# Connectors.net
KiCad netlist of a schematic drawn in Altium Designer
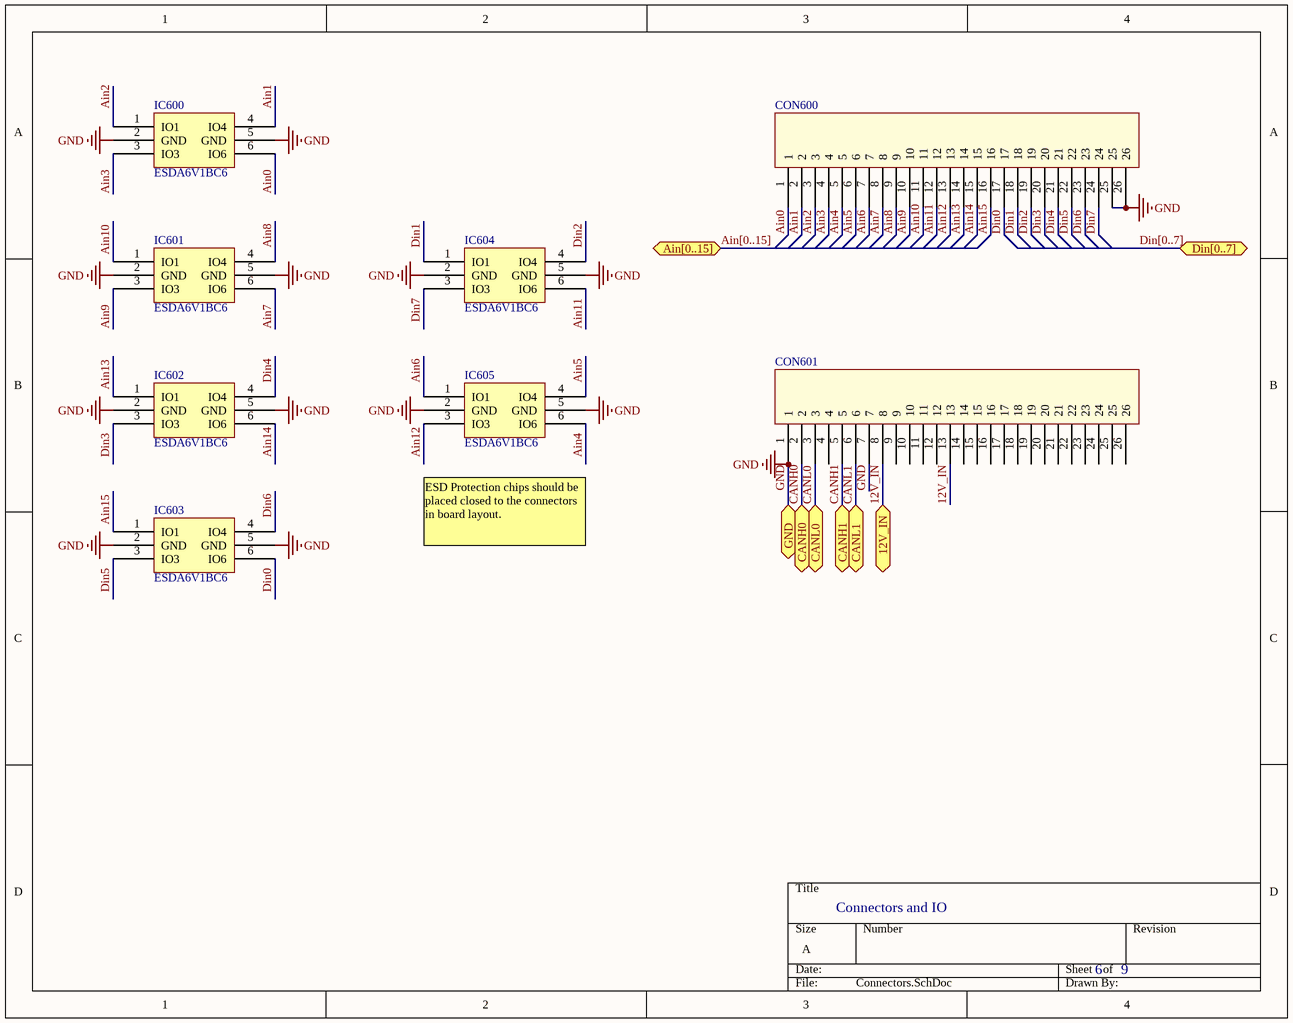
[diagram p0: Connectors.SchDoc]

(export (version "E")
  (design (tool "Eeschema 10.0.6"))
  (components
    (comp (ref "CON600")
      (value "26 Pin Conn")
      (footprint "AMP SuperSeal 1.0 26pin")
      (description "AMP SuperSeal 1.0 26 Pin")
      (libsource (lib "Components") (part "AMP_26Pin"))
    )
    (comp (ref "CON601")
      (value "26 Pin Conn")
      (footprint "AMP SuperSeal 1.0 26pin")
      (description "AMP SuperSeal 1.0 26 Pin")
      (libsource (lib "Components") (part "AMP_26Pin"))
    )
    (comp (ref "IC600")
      (value "ESDA6V1BC6")
      (footprint "SOT23-6L")
      (description "4 channel bi directional ESD protection")
      (libsource (lib "Components") (part "ESDA6V1BC6"))
    )
    (comp (ref "IC601")
      (value "ESDA6V1BC6")
      (footprint "SOT23-6L")
      (description "4 channel bi directional ESD protection")
      (libsource (lib "Components") (part "ESDA6V1BC6"))
    )
    (comp (ref "IC602")
      (value "ESDA6V1BC6")
      (footprint "SOT23-6L")
      (description "4 channel bi directional ESD protection")
      (libsource (lib "Components") (part "ESDA6V1BC6"))
    )
    (comp (ref "IC603")
      (value "ESDA6V1BC6")
      (footprint "SOT23-6L")
      (description "4 channel bi directional ESD protection")
      (libsource (lib "Components") (part "ESDA6V1BC6"))
    )
    (comp (ref "IC604")
      (value "ESDA6V1BC6")
      (footprint "SOT23-6L")
      (description "4 channel bi directional ESD protection")
      (libsource (lib "Components") (part "ESDA6V1BC6"))
    )
    (comp (ref "IC605")
      (value "ESDA6V1BC6")
      (footprint "SOT23-6L")
      (description "4 channel bi directional ESD protection")
      (libsource (lib "Components") (part "ESDA6V1BC6"))
    )
  )
  (nets
    (net (code "1") (name "/12V_IN") (class "Default")
      (node (ref "CON601") (pin "13") (pinfunction "13_13") (pintype "passive"))
      (node (ref "CON601") (pin "8") (pinfunction "8_8") (pintype "passive"))
    )
    (net (code "2") (name "/Ain0") (class "Default")
      (node (ref "CON600") (pin "1") (pinfunction "1_1") (pintype "passive"))
      (node (ref "IC600") (pin "6") (pinfunction "IO6_6") (pintype "passive"))
    )
    (net (code "3") (name "/Ain1") (class "Default")
      (node (ref "CON600") (pin "2") (pinfunction "2_2") (pintype "passive"))
      (node (ref "IC600") (pin "4") (pinfunction "IO4_4") (pintype "passive"))
    )
    (net (code "4") (name "/Ain2") (class "Default")
      (node (ref "CON600") (pin "3") (pinfunction "3_3") (pintype "passive"))
      (node (ref "IC600") (pin "1") (pinfunction "IO1_1") (pintype "passive"))
    )
    (net (code "5") (name "/Ain3") (class "Default")
      (node (ref "CON600") (pin "4") (pinfunction "4_4") (pintype "passive"))
      (node (ref "IC600") (pin "3") (pinfunction "IO3_3") (pintype "passive"))
    )
    (net (code "6") (name "/Ain4") (class "Default")
      (node (ref "CON600") (pin "5") (pinfunction "5_5") (pintype "passive"))
      (node (ref "IC605") (pin "6") (pinfunction "IO6_6") (pintype "passive"))
    )
    (net (code "7") (name "/Ain5") (class "Default")
      (node (ref "CON600") (pin "6") (pinfunction "6_6") (pintype "passive"))
      (node (ref "IC605") (pin "4") (pinfunction "IO4_4") (pintype "passive"))
    )
    (net (code "8") (name "/Ain6") (class "Default")
      (node (ref "CON600") (pin "7") (pinfunction "7_7") (pintype "passive"))
      (node (ref "IC605") (pin "1") (pinfunction "IO1_1") (pintype "passive"))
    )
    (net (code "9") (name "/Ain7") (class "Default")
      (node (ref "CON600") (pin "8") (pinfunction "8_8") (pintype "passive"))
      (node (ref "IC601") (pin "6") (pinfunction "IO6_6") (pintype "passive"))
    )
    (net (code "10") (name "/Ain8") (class "Default")
      (node (ref "CON600") (pin "9") (pinfunction "9_9") (pintype "passive"))
      (node (ref "IC601") (pin "4") (pinfunction "IO4_4") (pintype "passive"))
    )
    (net (code "11") (name "/Ain9") (class "Default")
      (node (ref "CON600") (pin "10") (pinfunction "10_10") (pintype "passive"))
      (node (ref "IC601") (pin "3") (pinfunction "IO3_3") (pintype "passive"))
    )
    (net (code "12") (name "/Ain10") (class "Default")
      (node (ref "CON600") (pin "11") (pinfunction "11_11") (pintype "passive"))
      (node (ref "IC601") (pin "1") (pinfunction "IO1_1") (pintype "passive"))
    )
    (net (code "13") (name "/Ain11") (class "Default")
      (node (ref "CON600") (pin "12") (pinfunction "12_12") (pintype "passive"))
      (node (ref "IC604") (pin "6") (pinfunction "IO6_6") (pintype "passive"))
    )
    (net (code "14") (name "/Ain12") (class "Default")
      (node (ref "CON600") (pin "13") (pinfunction "13_13") (pintype "passive"))
      (node (ref "IC605") (pin "3") (pinfunction "IO3_3") (pintype "passive"))
    )
    (net (code "15") (name "/Ain13") (class "Default")
      (node (ref "CON600") (pin "14") (pinfunction "14_14") (pintype "passive"))
      (node (ref "IC602") (pin "1") (pinfunction "IO1_1") (pintype "passive"))
    )
    (net (code "16") (name "/Ain14") (class "Default")
      (node (ref "CON600") (pin "15") (pinfunction "15_15") (pintype "passive"))
      (node (ref "IC602") (pin "6") (pinfunction "IO6_6") (pintype "passive"))
    )
    (net (code "17") (name "/Ain15") (class "Default")
      (node (ref "CON600") (pin "16") (pinfunction "16_16") (pintype "passive"))
      (node (ref "IC603") (pin "1") (pinfunction "IO1_1") (pintype "passive"))
    )
    (net (code "19") (name "/CANH0") (class "Default")
      (node (ref "CON601") (pin "2") (pinfunction "2_2") (pintype "passive"))
    )
    (net (code "20") (name "/CANH1") (class "Default")
      (node (ref "CON601") (pin "5") (pinfunction "5_5") (pintype "passive"))
    )
    (net (code "21") (name "/CANL0") (class "Default")
      (node (ref "CON601") (pin "3") (pinfunction "3_3") (pintype "passive"))
    )
    (net (code "22") (name "/CANL1") (class "Default")
      (node (ref "CON601") (pin "6") (pinfunction "6_6") (pintype "passive"))
    )
    (net (code "23") (name "/Din0") (class "Default")
      (node (ref "CON600") (pin "17") (pinfunction "17_17") (pintype "passive"))
      (node (ref "IC603") (pin "6") (pinfunction "IO6_6") (pintype "passive"))
    )
    (net (code "24") (name "/Din1") (class "Default")
      (node (ref "CON600") (pin "18") (pinfunction "18_18") (pintype "passive"))
      (node (ref "IC604") (pin "1") (pinfunction "IO1_1") (pintype "passive"))
    )
    (net (code "25") (name "/Din2") (class "Default")
      (node (ref "CON600") (pin "19") (pinfunction "19_19") (pintype "passive"))
      (node (ref "IC604") (pin "4") (pinfunction "IO4_4") (pintype "passive"))
    )
    (net (code "26") (name "/Din3") (class "Default")
      (node (ref "CON600") (pin "20") (pinfunction "20_20") (pintype "passive"))
      (node (ref "IC602") (pin "3") (pinfunction "IO3_3") (pintype "passive"))
    )
    (net (code "27") (name "/Din4") (class "Default")
      (node (ref "CON600") (pin "21") (pinfunction "21_21") (pintype "passive"))
      (node (ref "IC602") (pin "4") (pinfunction "IO4_4") (pintype "passive"))
    )
    (net (code "28") (name "/Din5") (class "Default")
      (node (ref "CON600") (pin "22") (pinfunction "22_22") (pintype "passive"))
      (node (ref "IC603") (pin "3") (pinfunction "IO3_3") (pintype "passive"))
    )
    (net (code "29") (name "/Din6") (class "Default")
      (node (ref "CON600") (pin "23") (pinfunction "23_23") (pintype "passive"))
      (node (ref "IC603") (pin "4") (pinfunction "IO4_4") (pintype "passive"))
    )
    (net (code "30") (name "/Din7") (class "Default")
      (node (ref "CON600") (pin "24") (pinfunction "24_24") (pintype "passive"))
      (node (ref "IC604") (pin "3") (pinfunction "IO3_3") (pintype "passive"))
    )
    (net (code "32") (name "GND") (class "Default")
      (node (ref "CON600") (pin "25") (pinfunction "25_25") (pintype "passive"))
      (node (ref "CON600") (pin "26") (pinfunction "26_26") (pintype "passive"))
      (node (ref "CON601") (pin "1") (pinfunction "1_1") (pintype "passive"))
      (node (ref "CON601") (pin "7") (pinfunction "7_7") (pintype "passive"))
      (node (ref "IC600") (pin "2") (pinfunction "GND_2") (pintype "passive"))
      (node (ref "IC600") (pin "5") (pinfunction "GND_5") (pintype "passive"))
      (node (ref "IC601") (pin "2") (pinfunction "GND_2") (pintype "passive"))
      (node (ref "IC601") (pin "5") (pinfunction "GND_5") (pintype "passive"))
      (node (ref "IC602") (pin "2") (pinfunction "GND_2") (pintype "passive"))
      (node (ref "IC602") (pin "5") (pinfunction "GND_5") (pintype "passive"))
      (node (ref "IC603") (pin "2") (pinfunction "GND_2") (pintype "passive"))
      (node (ref "IC603") (pin "5") (pinfunction "GND_5") (pintype "passive"))
      (node (ref "IC604") (pin "2") (pinfunction "GND_2") (pintype "passive"))
      (node (ref "IC604") (pin "5") (pinfunction "GND_5") (pintype "passive"))
      (node (ref "IC605") (pin "2") (pinfunction "GND_2") (pintype "passive"))
      (node (ref "IC605") (pin "5") (pinfunction "GND_5") (pintype "passive"))
    )
    (net (code "33") (name "unconnected-(CON601-Pad4)") (class "Default")
      (node (ref "CON601") (pin "4") (pinfunction "4_4") (pintype "passive"))
    )
    (net (code "34") (name "unconnected-(CON601-Pad9)") (class "Default")
      (node (ref "CON601") (pin "9") (pinfunction "9_9") (pintype "passive"))
    )
    (net (code "35") (name "unconnected-(CON601-Pad10)") (class "Default")
      (node (ref "CON601") (pin "10") (pinfunction "10_10") (pintype "passive"))
    )
    (net (code "36") (name "unconnected-(CON601-Pad11)") (class "Default")
      (node (ref "CON601") (pin "11") (pinfunction "11_11") (pintype "passive"))
    )
    (net (code "37") (name "unconnected-(CON601-Pad12)") (class "Default")
      (node (ref "CON601") (pin "12") (pinfunction "12_12") (pintype "passive"))
    )
    (net (code "38") (name "unconnected-(CON601-Pad14)") (class "Default")
      (node (ref "CON601") (pin "14") (pinfunction "14_14") (pintype "passive"))
    )
    (net (code "39") (name "unconnected-(CON601-Pad15)") (class "Default")
      (node (ref "CON601") (pin "15") (pinfunction "15_15") (pintype "passive"))
    )
    (net (code "40") (name "unconnected-(CON601-Pad16)") (class "Default")
      (node (ref "CON601") (pin "16") (pinfunction "16_16") (pintype "passive"))
    )
    (net (code "41") (name "unconnected-(CON601-Pad17)") (class "Default")
      (node (ref "CON601") (pin "17") (pinfunction "17_17") (pintype "passive"))
    )
    (net (code "42") (name "unconnected-(CON601-Pad18)") (class "Default")
      (node (ref "CON601") (pin "18") (pinfunction "18_18") (pintype "passive"))
    )
    (net (code "43") (name "unconnected-(CON601-Pad19)") (class "Default")
      (node (ref "CON601") (pin "19") (pinfunction "19_19") (pintype "passive"))
    )
    (net (code "44") (name "unconnected-(CON601-Pad20)") (class "Default")
      (node (ref "CON601") (pin "20") (pinfunction "20_20") (pintype "passive"))
    )
    (net (code "45") (name "unconnected-(CON601-Pad21)") (class "Default")
      (node (ref "CON601") (pin "21") (pinfunction "21_21") (pintype "passive"))
    )
    (net (code "46") (name "unconnected-(CON601-Pad22)") (class "Default")
      (node (ref "CON601") (pin "22") (pinfunction "22_22") (pintype "passive"))
    )
    (net (code "47") (name "unconnected-(CON601-Pad23)") (class "Default")
      (node (ref "CON601") (pin "23") (pinfunction "23_23") (pintype "passive"))
    )
    (net (code "48") (name "unconnected-(CON601-Pad24)") (class "Default")
      (node (ref "CON601") (pin "24") (pinfunction "24_24") (pintype "passive"))
    )
    (net (code "49") (name "unconnected-(CON601-Pad25)") (class "Default")
      (node (ref "CON601") (pin "25") (pinfunction "25_25") (pintype "passive"))
    )
    (net (code "50") (name "unconnected-(CON601-Pad26)") (class "Default")
      (node (ref "CON601") (pin "26") (pinfunction "26_26") (pintype "passive"))
    )
  )
)
